# MultiBoard_Digital_Connector.net
KiCad netlist of a schematic drawn in Altium Designer
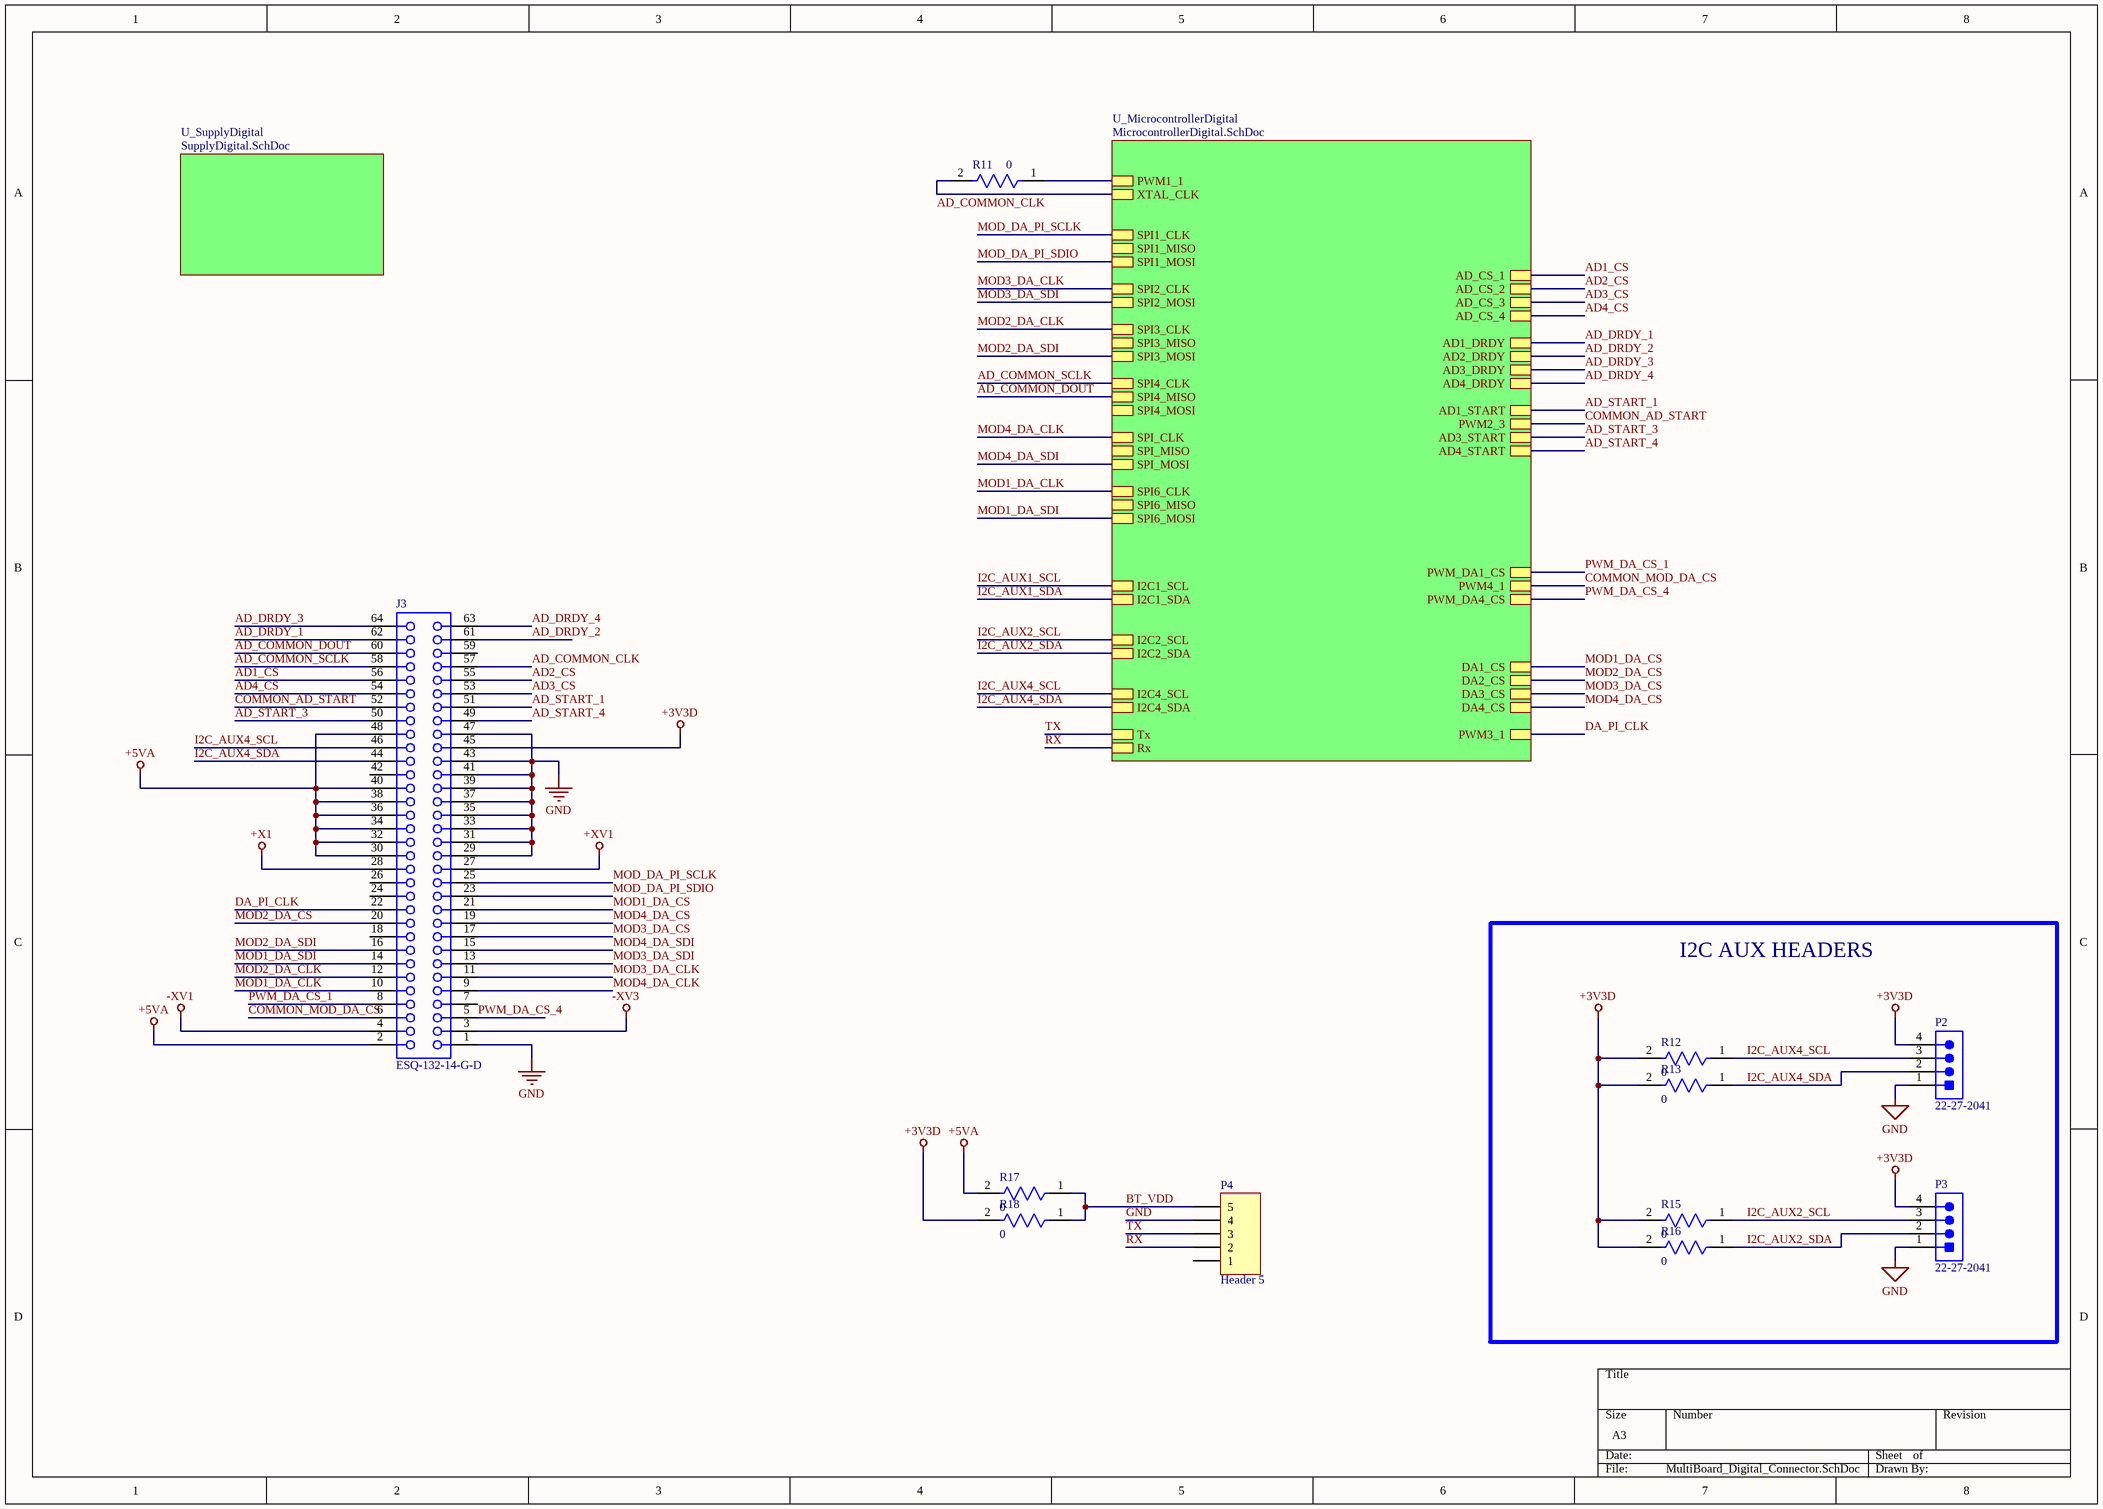
[diagram p0: MultiBoard_Digital_Connector.SchDoc]

(export (version "E")
  (design (tool "Eeschema 10.0.6"))
  (components
    (comp (ref "J3")
      (value "ESQ-132-14-G-D")
      (footprint "SMTC-ESQ-132-14-X-D")
      (fields (field (name "MANUFACTURER") "Samtec"))
      (libsource (lib "Altium Content Vault") (part "SMTC-ESQ-132-14-X-D"))
    )
    (comp (ref "P2")
      (value "22-27-2041")
      (footprint "MOLX-22-27-2041_V")
      (description "Male Header, Pitch 2.54 mm, 1 x 4 Position, Height 11.7 mm, Tail Length 3.56 mm, RoHS, Bulk")
      (fields (field (name "MANUFACTURER") "Molex"))
      (libsource (lib "Altium Content Vault") (part "CN-1P-M-R4"))
    )
    (comp (ref "P3")
      (value "22-27-2041")
      (footprint "MOLX-22-27-2041_V")
      (description "Male Header, Pitch 2.54 mm, 1 x 4 Position, Height 11.7 mm, Tail Length 3.56 mm, RoHS, Bulk")
      (fields (field (name "MANUFACTURER") "Molex"))
      (libsource (lib "Altium Content Vault") (part "CN-1P-M-R4"))
    )
    (comp (ref "P4")
      (value "Header 5")
      (footprint "HDR1X5")
      (description "Header, 5-Pin")
      (fields (field (name "PUBLISHER") "Altium Limited"))
      (libsource (lib "Miscellaneous Connectors") (part "Header 5"))
    )
    (comp (ref "R11")
      (value "0")
      (footprint "FP-RR1220-MFG")
      (description "49.9Ω ±0.5% 0.1W 1/10W Chip Resistor 0805 (2012 Metric) Thin Film")
      (fields (field (name "TOLERANCE") "0.5%"))
      (libsource (lib "Altium Content Vault") (part "1029c3af85768c4190bb7ad29bc67b5"))
    )
    (comp (ref "R12")
      (value "0")
      (footprint "FP-RR1220-MFG")
      (description "49.9Ω ±0.5% 0.1W 1/10W Chip Resistor 0805 (2012 Metric) Thin Film")
      (fields (field (name "TOLERANCE") "0.5%"))
      (libsource (lib "Altium Content Vault") (part "1029c3af85768c4190bb7ad29bc67b5"))
    )
    (comp (ref "R13")
      (value "0")
      (footprint "FP-RR1220-MFG")
      (description "49.9Ω ±0.5% 0.1W 1/10W Chip Resistor 0805 (2012 Metric) Thin Film")
      (fields (field (name "TOLERANCE") "0.5%"))
      (libsource (lib "Altium Content Vault") (part "1029c3af85768c4190bb7ad29bc67b5"))
    )
    (comp (ref "R15")
      (value "0")
      (footprint "FP-RR1220-MFG")
      (description "49.9Ω ±0.5% 0.1W 1/10W Chip Resistor 0805 (2012 Metric) Thin Film")
      (fields (field (name "TOLERANCE") "0.5%"))
      (libsource (lib "Altium Content Vault") (part "1029c3af85768c4190bb7ad29bc67b5"))
    )
    (comp (ref "R16")
      (value "0")
      (footprint "FP-RR1220-MFG")
      (description "49.9Ω ±0.5% 0.1W 1/10W Chip Resistor 0805 (2012 Metric) Thin Film")
      (fields (field (name "TOLERANCE") "0.5%"))
      (libsource (lib "Altium Content Vault") (part "1029c3af85768c4190bb7ad29bc67b5"))
    )
    (comp (ref "R17")
      (value "0")
      (footprint "FP-RR1220-MFG")
      (description "49.9Ω ±0.5% 0.1W 1/10W Chip Resistor 0805 (2012 Metric) Thin Film")
      (fields (field (name "TOLERANCE") "0.5%"))
      (libsource (lib "Altium Content Vault") (part "1029c3af85768c4190bb7ad29bc67b5"))
    )
    (comp (ref "R18")
      (value "0")
      (footprint "FP-RR1220-MFG")
      (description "49.9Ω ±0.5% 0.1W 1/10W Chip Resistor 0805 (2012 Metric) Thin Film")
      (fields (field (name "TOLERANCE") "0.5%"))
      (libsource (lib "Altium Content Vault") (part "1029c3af85768c4190bb7ad29bc67b5"))
    )
  )
  (nets
    (net (code "1") (name "+3V3D") (class "Default")
      (node (ref "J3") (pin "45") (pinfunction "45_45") (pintype "passive"))
      (node (ref "P2") (pin "4") (pinfunction "4_4") (pintype "passive"))
      (node (ref "P3") (pin "4") (pinfunction "4_4") (pintype "passive"))
      (node (ref "R12") (pin "2") (pinfunction "2_2") (pintype "passive"))
      (node (ref "R13") (pin "2") (pinfunction "2_2") (pintype "passive"))
      (node (ref "R15") (pin "2") (pinfunction "2_2") (pintype "passive"))
      (node (ref "R16") (pin "2") (pinfunction "2_2") (pintype "passive"))
      (node (ref "R18") (pin "2") (pinfunction "2_2") (pintype "passive"))
    )
    (net (code "2") (name "+5VA") (class "Default")
      (node (ref "J3") (pin "2") (pinfunction "2_2") (pintype "passive"))
      (node (ref "J3") (pin "30") (pinfunction "30_30") (pintype "passive"))
      (node (ref "J3") (pin "32") (pinfunction "32_32") (pintype "passive"))
      (node (ref "J3") (pin "34") (pinfunction "34_34") (pintype "passive"))
      (node (ref "J3") (pin "36") (pinfunction "36_36") (pintype "passive"))
      (node (ref "J3") (pin "38") (pinfunction "38_38") (pintype "passive"))
      (node (ref "J3") (pin "40") (pinfunction "40_40") (pintype "passive"))
      (node (ref "J3") (pin "48") (pinfunction "48_48") (pintype "passive"))
      (node (ref "R17") (pin "2") (pinfunction "2_2") (pintype "passive"))
    )
    (net (code "3") (name "+X1") (class "Default")
      (node (ref "J3") (pin "28") (pinfunction "28_28") (pintype "passive"))
    )
    (net (code "4") (name "+XV1") (class "Default")
      (node (ref "J3") (pin "27") (pinfunction "27_27") (pintype "passive"))
    )
    (net (code "5") (name "-XV1") (class "Default")
      (node (ref "J3") (pin "4") (pinfunction "4_4") (pintype "passive"))
    )
    (net (code "6") (name "-XV3") (class "Default")
      (node (ref "J3") (pin "3") (pinfunction "3_3") (pintype "passive"))
    )
    (net (code "7") (name "/AD1_CS") (class "Default")
      (node (ref "J3") (pin "56") (pinfunction "56_56") (pintype "passive"))
    )
    (net (code "8") (name "/AD2_CS") (class "Default")
      (node (ref "J3") (pin "55") (pinfunction "55_55") (pintype "passive"))
    )
    (net (code "9") (name "/AD3_CS") (class "Default")
      (node (ref "J3") (pin "53") (pinfunction "53_53") (pintype "passive"))
    )
    (net (code "10") (name "/AD4_CS") (class "Default")
      (node (ref "J3") (pin "54") (pinfunction "54_54") (pintype "passive"))
    )
    (net (code "11") (name "/AD_COMMON_CLK") (class "Default")
      (node (ref "J3") (pin "57") (pinfunction "57_57") (pintype "passive"))
      (node (ref "R11") (pin "2") (pinfunction "2_2") (pintype "passive"))
    )
    (net (code "12") (name "/AD_COMMON_DOUT") (class "Default")
      (node (ref "J3") (pin "60") (pinfunction "60_60") (pintype "passive"))
    )
    (net (code "13") (name "/AD_COMMON_SCLK") (class "Default")
      (node (ref "J3") (pin "58") (pinfunction "58_58") (pintype "passive"))
    )
    (net (code "14") (name "/AD_DRDY_1") (class "Default")
      (node (ref "J3") (pin "62") (pinfunction "62_62") (pintype "passive"))
    )
    (net (code "15") (name "/AD_DRDY_2") (class "Default")
      (node (ref "J3") (pin "61") (pinfunction "61_61") (pintype "passive"))
    )
    (net (code "16") (name "/AD_DRDY_3") (class "Default")
      (node (ref "J3") (pin "64") (pinfunction "64_64") (pintype "passive"))
    )
    (net (code "17") (name "/AD_DRDY_4") (class "Default")
      (node (ref "J3") (pin "63") (pinfunction "63_63") (pintype "passive"))
    )
    (net (code "18") (name "/AD_START_1") (class "Default")
      (node (ref "J3") (pin "51") (pinfunction "51_51") (pintype "passive"))
    )
    (net (code "19") (name "/AD_START_3") (class "Default")
      (node (ref "J3") (pin "50") (pinfunction "50_50") (pintype "passive"))
    )
    (net (code "20") (name "/AD_START_4") (class "Default")
      (node (ref "J3") (pin "49") (pinfunction "49_49") (pintype "passive"))
    )
    (net (code "21") (name "/BT_VDD") (class "Default")
      (node (ref "P4") (pin "5") (pinfunction "5_5") (pintype "passive"))
      (node (ref "R17") (pin "1") (pinfunction "1_1") (pintype "passive"))
      (node (ref "R18") (pin "1") (pinfunction "1_1") (pintype "passive"))
    )
    (net (code "22") (name "/COMMON_AD_START") (class "Default")
      (node (ref "J3") (pin "52") (pinfunction "52_52") (pintype "passive"))
    )
    (net (code "23") (name "/COMMON_MOD_DA_CS") (class "Default")
      (node (ref "J3") (pin "6") (pinfunction "6_6") (pintype "passive"))
    )
    (net (code "24") (name "/DA_PI_CLK") (class "Default")
      (node (ref "J3") (pin "22") (pinfunction "22_22") (pintype "passive"))
    )
    (net (code "27") (name "/I2C_AUX2_SCL") (class "Default")
      (node (ref "P3") (pin "3") (pinfunction "3_3") (pintype "passive"))
      (node (ref "R15") (pin "1") (pinfunction "1_1") (pintype "passive"))
    )
    (net (code "28") (name "/I2C_AUX2_SDA") (class "Default")
      (node (ref "P3") (pin "2") (pinfunction "2_2") (pintype "passive"))
      (node (ref "R16") (pin "1") (pinfunction "1_1") (pintype "passive"))
    )
    (net (code "29") (name "/I2C_AUX4_SCL") (class "Default")
      (node (ref "J3") (pin "46") (pinfunction "46_46") (pintype "passive"))
      (node (ref "P2") (pin "3") (pinfunction "3_3") (pintype "passive"))
      (node (ref "R12") (pin "1") (pinfunction "1_1") (pintype "passive"))
    )
    (net (code "30") (name "/I2C_AUX4_SDA") (class "Default")
      (node (ref "J3") (pin "44") (pinfunction "44_44") (pintype "passive"))
      (node (ref "P2") (pin "2") (pinfunction "2_2") (pintype "passive"))
      (node (ref "R13") (pin "1") (pinfunction "1_1") (pintype "passive"))
    )
    (net (code "31") (name "/MOD1_DA_CLK") (class "Default")
      (node (ref "J3") (pin "10") (pinfunction "10_10") (pintype "passive"))
    )
    (net (code "32") (name "/MOD1_DA_CS") (class "Default")
      (node (ref "J3") (pin "21") (pinfunction "21_21") (pintype "passive"))
    )
    (net (code "33") (name "/MOD1_DA_SDI") (class "Default")
      (node (ref "J3") (pin "14") (pinfunction "14_14") (pintype "passive"))
    )
    (net (code "34") (name "/MOD2_DA_CLK") (class "Default")
      (node (ref "J3") (pin "12") (pinfunction "12_12") (pintype "passive"))
    )
    (net (code "35") (name "/MOD2_DA_CS") (class "Default")
      (node (ref "J3") (pin "20") (pinfunction "20_20") (pintype "passive"))
    )
    (net (code "36") (name "/MOD2_DA_SDI") (class "Default")
      (node (ref "J3") (pin "16") (pinfunction "16_16") (pintype "passive"))
    )
    (net (code "37") (name "/MOD3_DA_CLK") (class "Default")
      (node (ref "J3") (pin "11") (pinfunction "11_11") (pintype "passive"))
    )
    (net (code "38") (name "/MOD3_DA_CS") (class "Default")
      (node (ref "J3") (pin "17") (pinfunction "17_17") (pintype "passive"))
    )
    (net (code "39") (name "/MOD3_DA_SDI") (class "Default")
      (node (ref "J3") (pin "13") (pinfunction "13_13") (pintype "passive"))
    )
    (net (code "40") (name "/MOD4_DA_CLK") (class "Default")
      (node (ref "J3") (pin "9") (pinfunction "9_9") (pintype "passive"))
    )
    (net (code "41") (name "/MOD4_DA_CS") (class "Default")
      (node (ref "J3") (pin "19") (pinfunction "19_19") (pintype "passive"))
    )
    (net (code "42") (name "/MOD4_DA_SDI") (class "Default")
      (node (ref "J3") (pin "15") (pinfunction "15_15") (pintype "passive"))
    )
    (net (code "43") (name "/MOD_DA_PI_SCLK") (class "Default")
      (node (ref "J3") (pin "25") (pinfunction "25_25") (pintype "passive"))
    )
    (net (code "44") (name "/MOD_DA_PI_SDIO") (class "Default")
      (node (ref "J3") (pin "23") (pinfunction "23_23") (pintype "passive"))
    )
    (net (code "45") (name "/PWM1_1") (class "Default")
      (node (ref "R11") (pin "1") (pinfunction "1_1") (pintype "passive"))
    )
    (net (code "46") (name "/PWM_DA_CS_1") (class "Default")
      (node (ref "J3") (pin "8") (pinfunction "8_8") (pintype "passive"))
    )
    (net (code "47") (name "/PWM_DA_CS_4") (class "Default")
      (node (ref "J3") (pin "5") (pinfunction "5_5") (pintype "passive"))
    )
    (net (code "48") (name "/RX") (class "Default")
      (node (ref "P4") (pin "2") (pinfunction "2_2") (pintype "passive"))
    )
    (net (code "54") (name "/TX") (class "Default")
      (node (ref "P4") (pin "3") (pinfunction "3_3") (pintype "passive"))
    )
    (net (code "55") (name "GND") (class "Default")
      (node (ref "J3") (pin "1") (pinfunction "1_1") (pintype "passive"))
      (node (ref "J3") (pin "29") (pinfunction "29_29") (pintype "passive"))
      (node (ref "J3") (pin "31") (pinfunction "31_31") (pintype "passive"))
      (node (ref "J3") (pin "33") (pinfunction "33_33") (pintype "passive"))
      (node (ref "J3") (pin "35") (pinfunction "35_35") (pintype "passive"))
      (node (ref "J3") (pin "37") (pinfunction "37_37") (pintype "passive"))
      (node (ref "J3") (pin "39") (pinfunction "39_39") (pintype "passive"))
      (node (ref "J3") (pin "41") (pinfunction "41_41") (pintype "passive"))
      (node (ref "J3") (pin "43") (pinfunction "43_43") (pintype "passive"))
      (node (ref "J3") (pin "47") (pinfunction "47_47") (pintype "passive"))
      (node (ref "P2") (pin "1") (pinfunction "1_1") (pintype "passive"))
      (node (ref "P3") (pin "1") (pinfunction "1_1") (pintype "passive"))
      (node (ref "P4") (pin "4") (pinfunction "4_4") (pintype "passive"))
    )
    (net (code "56") (name "unconnected-(J3-Pad7)") (class "Default")
      (node (ref "J3") (pin "7") (pinfunction "7_7") (pintype "passive"))
    )
    (net (code "57") (name "unconnected-(J3-Pad18)") (class "Default")
      (node (ref "J3") (pin "18") (pinfunction "18_18") (pintype "passive"))
    )
    (net (code "58") (name "unconnected-(J3-Pad24)") (class "Default")
      (node (ref "J3") (pin "24") (pinfunction "24_24") (pintype "passive"))
    )
    (net (code "59") (name "unconnected-(J3-Pad26)") (class "Default")
      (node (ref "J3") (pin "26") (pinfunction "26_26") (pintype "passive"))
    )
    (net (code "60") (name "unconnected-(J3-Pad42)") (class "Default")
      (node (ref "J3") (pin "42") (pinfunction "42_42") (pintype "passive"))
    )
    (net (code "61") (name "unconnected-(J3-Pad59)") (class "Default")
      (node (ref "J3") (pin "59") (pinfunction "59_59") (pintype "passive"))
    )
    (net (code "62") (name "unconnected-(P4-Pad1)") (class "Default")
      (node (ref "P4") (pin "1") (pinfunction "1_1") (pintype "passive"))
    )
  )
)
